# Interface_Board_v1_2.net
KiCad netlist of a schematic drawn in EAGLE
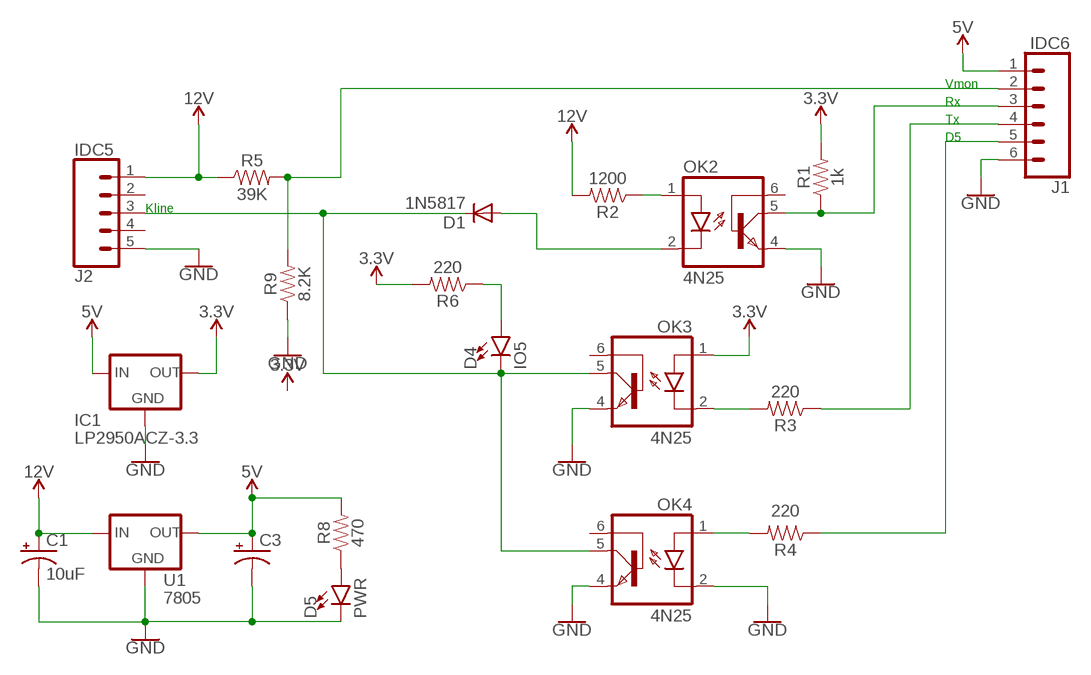
[diagram p0: schematic, sheet 1]

(export (version "E")
  (design (tool "Eeschema 10.0.6"))
  (components
    (comp (ref "C1")
      (value "10uF")
      (footprint "eagle-import:CPOL-RADIAL-2.5MM-5MM")
      (libsource (lib "eagle-import") (part "10UF-POLAR-RADIAL-2.5MM-25V-20%"))
    )
    (comp (ref "C3")
      (value "10uF")
      (footprint "eagle-import:CPOL-RADIAL-2.5MM-5MM")
      (libsource (lib "eagle-import") (part "10UF-POLAR-RADIAL-2.5MM-25V-20%"))
    )
    (comp (ref "D1")
      (value "1N5817")
      (footprint "eagle-import:DO41-10")
      (libsource (lib "eagle-import") (part "1N4004"))
    )
    (comp (ref "D4")
      (value "IO5")
      (footprint "eagle-import:LED_5MM")
      (libsource (lib "eagle-import") (part "LED5MM"))
    )
    (comp (ref "D5")
      (value "PWR")
      (footprint "eagle-import:LED_5MM")
      (libsource (lib "eagle-import") (part "LED5MM"))
    )
    (comp (ref "IC1")
      (value "LP2950ACZ-3.3")
      (footprint "eagle-import:TO92")
      (libsource (lib "eagle-import") (part "LP2950?ACZ-3.3"))
    )
    (comp (ref "J1")
      (value "IDC6")
      (footprint "eagle-import:1X06_LONGPADS")
      (libsource (lib "eagle-import") (part "CONN_06LONGPADS"))
    )
    (comp (ref "J2")
      (value "IDC5")
      (footprint "eagle-import:1X05")
      (libsource (lib "eagle-import") (part "CONN_05"))
    )
    (comp (ref "OK2")
      (value "4N25")
      (footprint "eagle-import:DIL06")
      (fields (field (name "MF") "FAIRCHILD SEMICONDUCTOR") (field (name "MPN") "4N35"))
      (libsource (lib "eagle-import") (part "4N35"))
    )
    (comp (ref "OK3")
      (value "4N25")
      (footprint "eagle-import:DIL06")
      (fields (field (name "MF") "FAIRCHILD SEMICONDUCTOR") (field (name "MPN") "4N35"))
      (libsource (lib "eagle-import") (part "4N35"))
    )
    (comp (ref "OK4")
      (value "4N25")
      (footprint "eagle-import:DIL06")
      (fields (field (name "MF") "FAIRCHILD SEMICONDUCTOR") (field (name "MPN") "4N35"))
      (libsource (lib "eagle-import") (part "4N35"))
    )
    (comp (ref "R1")
      (value "1k")
      (footprint "eagle-import:AXIAL-0.3")
      (libsource (lib "eagle-import") (part "1KOHM-HORIZ-1/4W-1%"))
    )
    (comp (ref "R2")
      (value "1200")
      (footprint "eagle-import:AXIAL-0.3")
      (libsource (lib "eagle-import") (part "1KOHM-HORIZ-1/4W-1%"))
    )
    (comp (ref "R3")
      (value "220")
      (footprint "eagle-import:AXIAL-0.3")
      (libsource (lib "eagle-import") (part "1KOHM-HORIZ-1/4W-1%"))
    )
    (comp (ref "R4")
      (value "220")
      (footprint "eagle-import:AXIAL-0.3")
      (libsource (lib "eagle-import") (part "1KOHM-HORIZ-1/4W-1%"))
    )
    (comp (ref "R5")
      (value "39K")
      (footprint "eagle-import:AXIAL-0.3")
      (libsource (lib "eagle-import") (part "1KOHM-HORIZ-1/4W-1%"))
    )
    (comp (ref "R6")
      (value "220")
      (footprint "eagle-import:AXIAL-0.3")
      (libsource (lib "eagle-import") (part "1KOHM-HORIZ-1/4W-1%"))
    )
    (comp (ref "R8")
      (value "470")
      (footprint "eagle-import:AXIAL-0.3")
      (libsource (lib "eagle-import") (part "1KOHM-HORIZ-1/4W-1%"))
    )
    (comp (ref "R9")
      (value "8.2K")
      (footprint "eagle-import:AXIAL-0.3")
      (libsource (lib "eagle-import") (part "1KOHM-HORIZ-1/4W-1%"))
    )
    (comp (ref "U1")
      (value "7805")
      (footprint "eagle-import:TO-220-ALT")
      (libsource (lib "eagle-import") (part "V_REG_78XX-TO-220"))
    )
  )
  (nets
    (net (code "1") (name "3.3V") (class "Default")
      (node (ref "IC1") (pin "1") (pinfunction "OUT_1") (pintype "passive"))
      (node (ref "OK3") (pin "1") (pinfunction "A_1") (pintype "passive"))
      (node (ref "R1") (pin "P$2") (pinfunction "2_P$2") (pintype "passive"))
      (node (ref "R6") (pin "P$2") (pinfunction "2_P$2") (pintype "passive"))
    )
    (net (code "2") (name "5V") (class "Default")
      (node (ref "C3") (pin "1") (pinfunction "+_1") (pintype "passive"))
      (node (ref "IC1") (pin "3") (pinfunction "IN_3") (pintype "input"))
      (node (ref "J1") (pin "1") (pinfunction "1_1") (pintype "passive"))
      (node (ref "R8") (pin "P$2") (pinfunction "2_P$2") (pintype "passive"))
      (node (ref "U1") (pin "OUT") (pinfunction "OUT_OUT") (pintype "passive"))
    )
    (net (code "3") (name "12V") (class "Default")
      (node (ref "C1") (pin "1") (pinfunction "+_1") (pintype "passive"))
      (node (ref "J2") (pin "1") (pinfunction "1_1") (pintype "passive"))
      (node (ref "R2") (pin "P$2") (pinfunction "2_P$2") (pintype "passive"))
      (node (ref "R5") (pin "P$1") (pinfunction "1_P$1") (pintype "passive"))
      (node (ref "U1") (pin "IN") (pinfunction "IN_IN") (pintype "input"))
    )
    (net (code "4") (name "GND") (class "Default")
      (node (ref "C1") (pin "2") (pinfunction "-_2") (pintype "passive"))
      (node (ref "C3") (pin "2") (pinfunction "-_2") (pintype "passive"))
      (node (ref "D5") (pin "K") (pinfunction "C_K") (pintype "passive"))
      (node (ref "IC1") (pin "2") (pinfunction "GND_2") (pintype "input"))
      (node (ref "J1") (pin "6") (pinfunction "6_6") (pintype "passive"))
      (node (ref "J2") (pin "5") (pinfunction "5_5") (pintype "passive"))
      (node (ref "OK2") (pin "4") (pinfunction "EMI_4") (pintype "passive"))
      (node (ref "OK3") (pin "4") (pinfunction "EMI_4") (pintype "passive"))
      (node (ref "OK4") (pin "2") (pinfunction "C_2") (pintype "passive"))
      (node (ref "OK4") (pin "4") (pinfunction "EMI_4") (pintype "passive"))
      (node (ref "R9") (pin "P$1") (pinfunction "1_P$1") (pintype "passive"))
      (node (ref "U1") (pin "GND") (pinfunction "GND_GND") (pintype "input"))
    )
    (net (code "5") (name "Net-(D4-C)") (class "Default")
      (node (ref "D1") (pin "C") (pinfunction "C_C") (pintype "passive"))
      (node (ref "D4") (pin "K") (pinfunction "C_K") (pintype "passive"))
      (node (ref "J2") (pin "3") (pinfunction "3_3") (pintype "passive"))
      (node (ref "OK3") (pin "5") (pinfunction "COL_5") (pintype "passive"))
      (node (ref "OK4") (pin "5") (pinfunction "COL_5") (pintype "passive"))
    )
    (net (code "6") (name "Net-(OK2-A)") (class "Default")
      (node (ref "OK2") (pin "1") (pinfunction "A_1") (pintype "passive"))
      (node (ref "R2") (pin "P$1") (pinfunction "1_P$1") (pintype "passive"))
    )
    (net (code "7") (name "Net-(OK2-C)") (class "Default")
      (node (ref "D1") (pin "A") (pinfunction "A_A") (pintype "passive"))
      (node (ref "OK2") (pin "2") (pinfunction "C_2") (pintype "passive"))
    )
    (net (code "8") (name "Net-(OK2-COL)") (class "Default")
      (node (ref "J1") (pin "3") (pinfunction "3_3") (pintype "passive"))
      (node (ref "OK2") (pin "5") (pinfunction "COL_5") (pintype "passive"))
      (node (ref "R1") (pin "P$1") (pinfunction "1_P$1") (pintype "passive"))
    )
    (net (code "9") (name "Net-(OK3-C)") (class "Default")
      (node (ref "OK3") (pin "2") (pinfunction "C_2") (pintype "passive"))
      (node (ref "R3") (pin "P$2") (pinfunction "2_P$2") (pintype "passive"))
    )
    (net (code "10") (name "Net-(OK4-A)") (class "Default")
      (node (ref "OK4") (pin "1") (pinfunction "A_1") (pintype "passive"))
      (node (ref "R4") (pin "P$2") (pinfunction "2_P$2") (pintype "passive"))
    )
    (net (code "11") (name "Net-(R3-1)") (class "Default")
      (node (ref "J1") (pin "4") (pinfunction "4_4") (pintype "passive"))
      (node (ref "R3") (pin "P$1") (pinfunction "1_P$1") (pintype "passive"))
    )
    (net (code "12") (name "Net-(R4-1)") (class "Default")
      (node (ref "J1") (pin "5") (pinfunction "5_5") (pintype "passive"))
      (node (ref "R4") (pin "P$1") (pinfunction "1_P$1") (pintype "passive"))
    )
    (net (code "13") (name "Net-(R5-2)") (class "Default")
      (node (ref "J1") (pin "2") (pinfunction "2_2") (pintype "passive"))
      (node (ref "R5") (pin "P$2") (pinfunction "2_P$2") (pintype "passive"))
      (node (ref "R9") (pin "P$2") (pinfunction "2_P$2") (pintype "passive"))
    )
    (net (code "14") (name "Net-(R6-1)") (class "Default")
      (node (ref "D4") (pin "A") (pinfunction "A_A") (pintype "passive"))
      (node (ref "R6") (pin "P$1") (pinfunction "1_P$1") (pintype "passive"))
    )
    (net (code "15") (name "Net-(R8-1)") (class "Default")
      (node (ref "D5") (pin "A") (pinfunction "A_A") (pintype "passive"))
      (node (ref "R8") (pin "P$1") (pinfunction "1_P$1") (pintype "passive"))
    )
    (net (code "16") (name "unconnected-(J2-Pad2)") (class "Default")
      (node (ref "J2") (pin "2") (pinfunction "2_2") (pintype "passive"))
    )
    (net (code "17") (name "unconnected-(J2-Pad4)") (class "Default")
      (node (ref "J2") (pin "4") (pinfunction "4_4") (pintype "passive"))
    )
    (net (code "18") (name "unconnected-(OK2-BAS-Pad6)") (class "Default")
      (node (ref "OK2") (pin "6") (pinfunction "BAS_6") (pintype "passive"))
    )
    (net (code "19") (name "unconnected-(OK3-BAS-Pad6)") (class "Default")
      (node (ref "OK3") (pin "6") (pinfunction "BAS_6") (pintype "passive"))
    )
    (net (code "20") (name "unconnected-(OK4-BAS-Pad6)") (class "Default")
      (node (ref "OK4") (pin "6") (pinfunction "BAS_6") (pintype "passive"))
    )
  )
)
